# eNode2.net
KiCad netlist of a schematic drawn in EAGLE
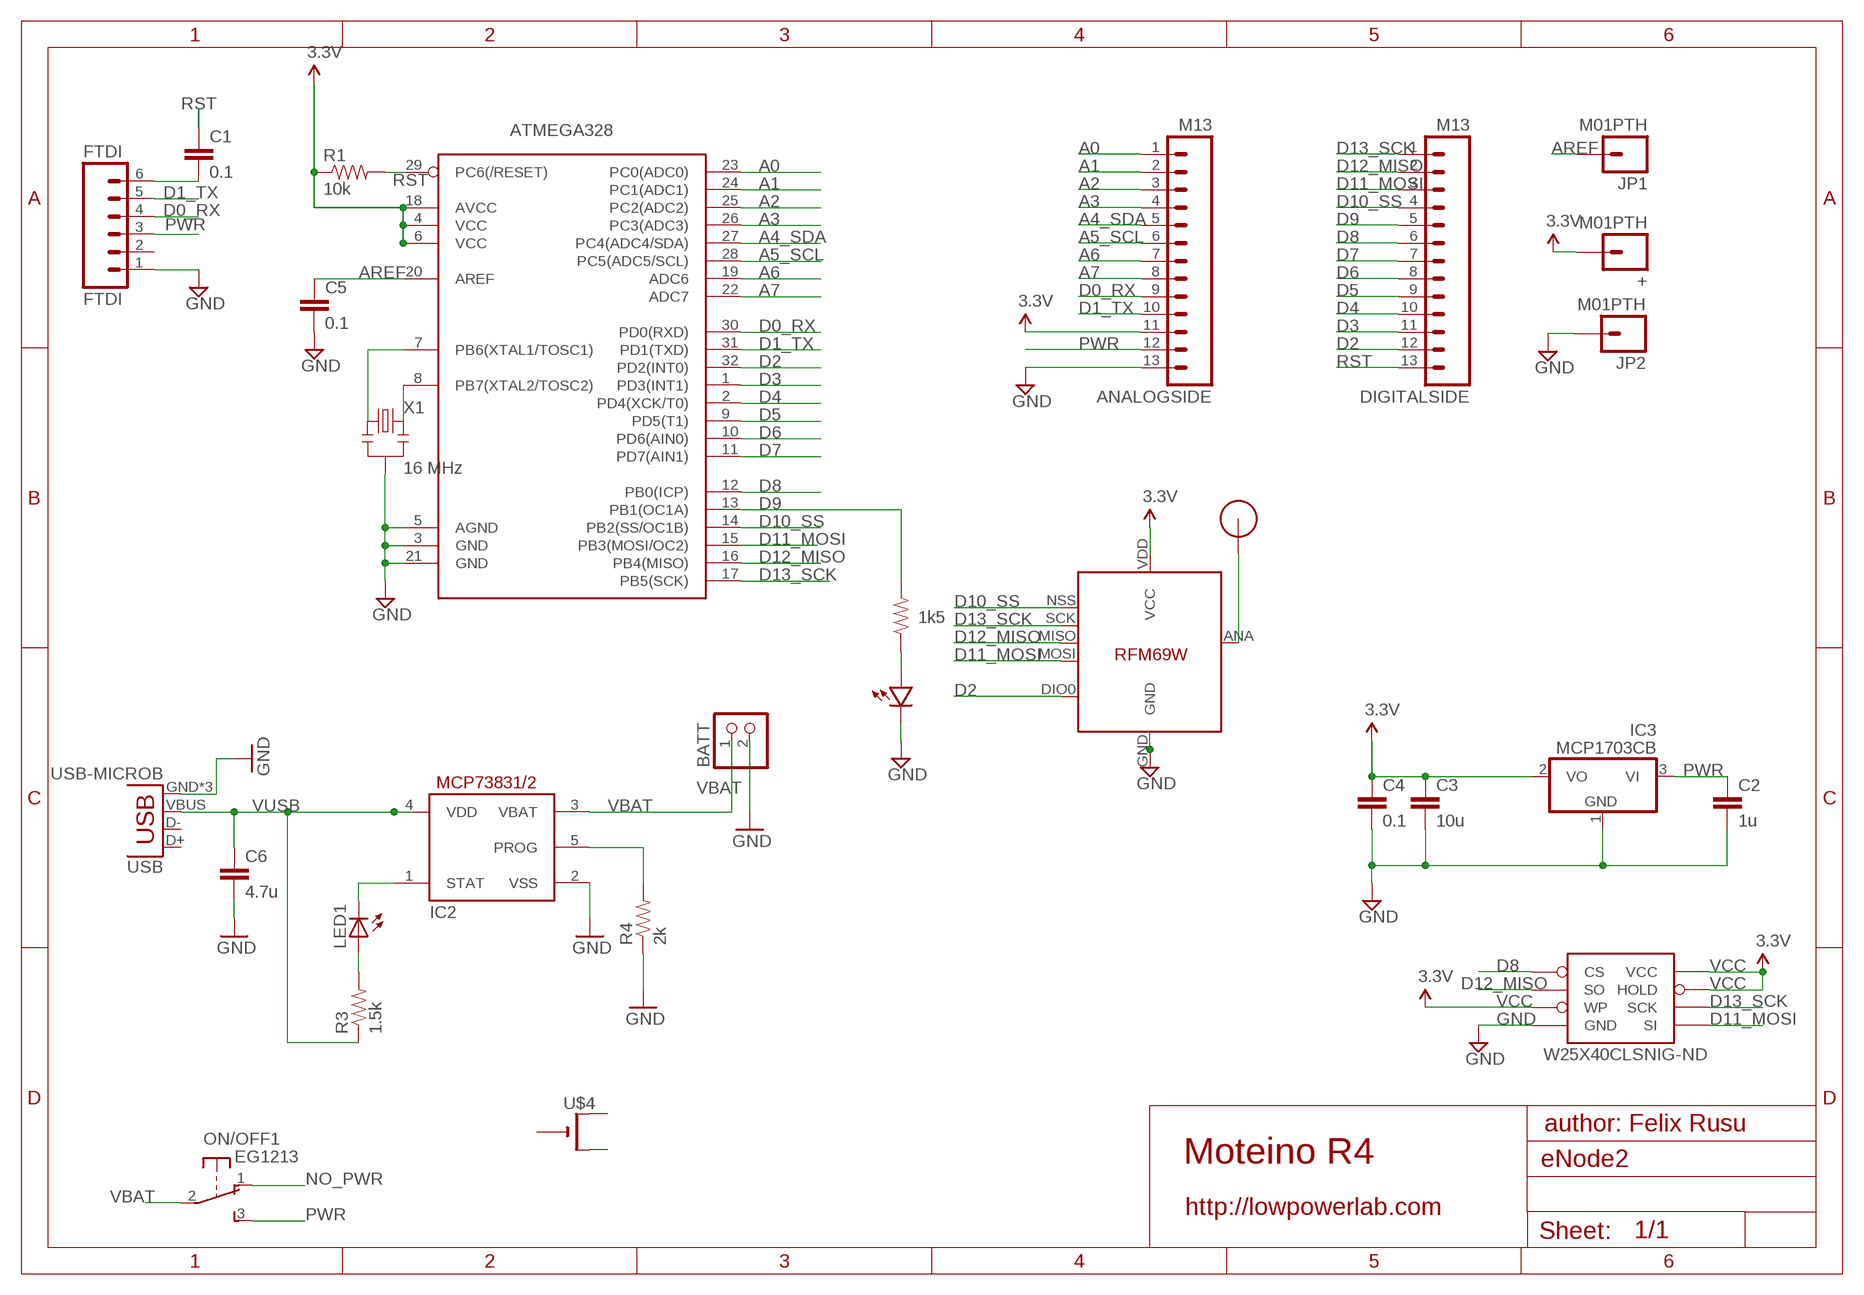
[diagram p0: schematic, sheet 1]

(export (version "E")
  (design (tool "Eeschema 10.0.6"))
  (components
    (comp (ref "+")
      (value "M01PTH")
      (footprint "eagle-import:1X01")
      (libsource (lib "eagle-import") (part "M01PTH"))
    )
    (comp (ref "ANALOGSIDE")
      (value "M13")
      (footprint "eagle-import:1X13")
      (libsource (lib "eagle-import") (part "M13"))
    )
    (comp (ref "ATMEGA328")
      (value "ATMega-328")
      (footprint "eagle-import:TQFP32-08")
      (libsource (lib "eagle-import") (part "ATMEGA168/328TQFP32"))
    )
    (comp (ref "BATT")
      (value "PINHD-1X2")
      (footprint "eagle-import:1X02")
      (libsource (lib "eagle-import") (part "PINHD-1X2"))
    )
    (comp (ref "C1")
      (value "0.1")
      (footprint "eagle-import:0603-CAP")
      (libsource (lib "eagle-import") (part "CAP0603-CAP"))
    )
    (comp (ref "C2")
      (value "1u")
      (footprint "eagle-import:0603-CAP")
      (libsource (lib "eagle-import") (part "CAP0603-CAP"))
    )
    (comp (ref "C3")
      (value "10u")
      (footprint "eagle-import:0805-CAP")
      (libsource (lib "eagle-import") (part "CAP0805-CAP"))
    )
    (comp (ref "C4")
      (value "0.1")
      (footprint "eagle-import:0603-CAP")
      (libsource (lib "eagle-import") (part "CAP0603-CAP"))
    )
    (comp (ref "C5")
      (value "0.1")
      (footprint "eagle-import:0603-CAP")
      (libsource (lib "eagle-import") (part "CAP0603-CAP"))
    )
    (comp (ref "C6")
      (value "4.7u")
      (footprint "eagle-import:0603-CAP")
      (libsource (lib "eagle-import") (part "SparkFun-Passives_CAP0603-CAP"))
    )
    (comp (ref "DIGITALSIDE")
      (value "M13")
      (footprint "eagle-import:1X13")
      (libsource (lib "eagle-import") (part "M13"))
    )
    (comp (ref "FTDI")
      (value "FTDI")
      (footprint "eagle-import:1X06")
      (libsource (lib "eagle-import") (part "M06SIP"))
    )
    (comp (ref "IC2")
      (value "MCP73831/OT")
      (footprint "eagle-import:SOT23-5L")
      (libsource (lib "eagle-import") (part "MCP73831/OT"))
    )
    (comp (ref "IC3")
      (value "MCP1703CB")
      (footprint "eagle-import:SOT23")
      (libsource (lib "eagle-import") (part "MCP1703CB"))
    )
    (comp (ref "JP1")
      (value "M01PTH")
      (footprint "eagle-import:1X01")
      (libsource (lib "eagle-import") (part "M01PTH"))
    )
    (comp (ref "JP2")
      (value "M01PTH")
      (footprint "eagle-import:1X01")
      (libsource (lib "eagle-import") (part "M01PTH"))
    )
    (comp (ref "LED1")
      (value "LEDCHIPLED_0603")
      (footprint "eagle-import:CHIPLED_0603")
      (libsource (lib "eagle-import") (part "LEDCHIPLED_0603"))
    )
    (comp (ref "ON/OFF")
      (value "EG1213")
      (footprint "eagle-import:EG1213")
      (libsource (lib "eagle-import") (part "EG1213"))
    )
    (comp (ref "R1")
      (value "10k")
      (footprint "eagle-import:0603-RES")
      (libsource (lib "eagle-import") (part "RESISTOR0603-RES"))
    )
    (comp (ref "R2")
      (value "1k5")
      (footprint "eagle-import:0603-RES")
      (libsource (lib "eagle-import") (part "RESISTOR0603-RES"))
    )
    (comp (ref "R3")
      (value "1.5k")
      (footprint "eagle-import:0603-RES")
      (libsource (lib "eagle-import") (part "SparkFun-Passives_RESISTOR0603-RES"))
    )
    (comp (ref "R4")
      (value "2k")
      (footprint "eagle-import:0603-RES")
      (libsource (lib "eagle-import") (part "SparkFun-Passives_RESISTOR0603-RES"))
    )
    (comp (ref "U$1")
      (value "RFM12B_ANTENNA")
      (footprint "eagle-import:RFM12B-ANTENNA")
      (libsource (lib "eagle-import") (part "RFM12B_ANTENNA"))
    )
    (comp (ref "U$2")
      (value "LED0603")
      (footprint "eagle-import:0603-LED")
      (libsource (lib "eagle-import") (part "LED0603"))
    )
    (comp (ref "U$4")
      (value "CR2032THM")
      (footprint "eagle-import:CR2032-THRU")
      (libsource (lib "eagle-import") (part "CR2032THM"))
    )
    (comp (ref "U$5")
      (value "RFM69")
      (footprint "eagle-import:RFM69W-MINPADS")
      (libsource (lib "eagle-import") (part "RFM69"))
    )
    (comp (ref "USB")
      (value "USB-MICROB")
      (footprint "eagle-import:USB-MICROB")
      (libsource (lib "eagle-import") (part "USB-MICROB"))
    )
    (comp (ref "W25X40CLSNIG-ND")
      (value "AT25F512BWIDE_5.3MM")
      (footprint "eagle-import:SO08WIDE")
      (libsource (lib "eagle-import") (part "AT25F512BWIDE_5.3MM"))
    )
    (comp (ref "X1")
      (value "16 MHz")
      (footprint "eagle-import:RESONATOR-SMD")
      (libsource (lib "eagle-import") (part "RESONATORSMD"))
    )
  )
  (nets
    (net (code "1") (name "/A0") (class "Default")
      (node (ref "ANALOGSIDE") (pin "1") (pinfunction "1_1") (pintype "passive"))
      (node (ref "ATMEGA328") (pin "23") (pinfunction "PC0(ADC0)_23") (pintype "bidirectional"))
    )
    (net (code "2") (name "/A1") (class "Default")
      (node (ref "ANALOGSIDE") (pin "2") (pinfunction "2_2") (pintype "passive"))
      (node (ref "ATMEGA328") (pin "24") (pinfunction "PC1(ADC1)_24") (pintype "bidirectional"))
    )
    (net (code "3") (name "/A2") (class "Default")
      (node (ref "ANALOGSIDE") (pin "3") (pinfunction "3_3") (pintype "passive"))
      (node (ref "ATMEGA328") (pin "25") (pinfunction "PC2(ADC2)_25") (pintype "bidirectional"))
    )
    (net (code "4") (name "/A3") (class "Default")
      (node (ref "ANALOGSIDE") (pin "4") (pinfunction "4_4") (pintype "passive"))
      (node (ref "ATMEGA328") (pin "26") (pinfunction "PC3(ADC3)_26") (pintype "bidirectional"))
    )
    (net (code "5") (name "/A4_SDA") (class "Default")
      (node (ref "ANALOGSIDE") (pin "5") (pinfunction "5_5") (pintype "passive"))
      (node (ref "ATMEGA328") (pin "27") (pinfunction "PC4(ADC4/SDA)_27") (pintype "bidirectional"))
    )
    (net (code "6") (name "/A5_SCL") (class "Default")
      (node (ref "ANALOGSIDE") (pin "6") (pinfunction "6_6") (pintype "passive"))
      (node (ref "ATMEGA328") (pin "28") (pinfunction "PC5(ADC5/SCL)_28") (pintype "bidirectional"))
    )
    (net (code "7") (name "/A6") (class "Default")
      (node (ref "ANALOGSIDE") (pin "7") (pinfunction "7_7") (pintype "passive"))
      (node (ref "ATMEGA328") (pin "19") (pinfunction "ADC6_19") (pintype "bidirectional"))
    )
    (net (code "8") (name "/A7") (class "Default")
      (node (ref "ANALOGSIDE") (pin "8") (pinfunction "8_8") (pintype "passive"))
      (node (ref "ATMEGA328") (pin "22") (pinfunction "ADC7_22") (pintype "bidirectional"))
    )
    (net (code "9") (name "/AREF") (class "Default")
      (node (ref "ATMEGA328") (pin "20") (pinfunction "AREF_20") (pintype "bidirectional"))
      (node (ref "C5") (pin "1") (pinfunction "1_1") (pintype "passive"))
      (node (ref "JP1") (pin "1") (pinfunction "1_1") (pintype "passive"))
    )
    (net (code "10") (name "/D0_RX") (class "Default")
      (node (ref "ANALOGSIDE") (pin "9") (pinfunction "9_9") (pintype "passive"))
      (node (ref "ATMEGA328") (pin "30") (pinfunction "PD0(RXD)_30") (pintype "bidirectional"))
      (node (ref "FTDI") (pin "4") (pinfunction "4_4") (pintype "passive"))
    )
    (net (code "11") (name "/D1_TX") (class "Default")
      (node (ref "ANALOGSIDE") (pin "10") (pinfunction "10_10") (pintype "passive"))
      (node (ref "ATMEGA328") (pin "31") (pinfunction "PD1(TXD)_31") (pintype "bidirectional"))
      (node (ref "FTDI") (pin "5") (pinfunction "5_5") (pintype "passive"))
    )
    (net (code "12") (name "/D2") (class "Default")
      (node (ref "ATMEGA328") (pin "32") (pinfunction "PD2(INT0)_32") (pintype "bidirectional"))
      (node (ref "DIGITALSIDE") (pin "12") (pinfunction "12_12") (pintype "passive"))
      (node (ref "U$5") (pin "DIO0") (pinfunction "DIO0_DIO0") (pintype "open_collector"))
    )
    (net (code "13") (name "/D3") (class "Default")
      (node (ref "ATMEGA328") (pin "1") (pinfunction "PD3(INT1)_1") (pintype "bidirectional"))
      (node (ref "DIGITALSIDE") (pin "11") (pinfunction "11_11") (pintype "passive"))
    )
    (net (code "14") (name "/D4") (class "Default")
      (node (ref "ATMEGA328") (pin "2") (pinfunction "PD4(XCK/T0)_2") (pintype "bidirectional"))
      (node (ref "DIGITALSIDE") (pin "10") (pinfunction "10_10") (pintype "passive"))
    )
    (net (code "15") (name "/D5") (class "Default")
      (node (ref "ATMEGA328") (pin "9") (pinfunction "PD5(T1)_9") (pintype "bidirectional"))
      (node (ref "DIGITALSIDE") (pin "9") (pinfunction "9_9") (pintype "passive"))
    )
    (net (code "16") (name "/D6") (class "Default")
      (node (ref "ATMEGA328") (pin "10") (pinfunction "PD6(AIN0)_10") (pintype "bidirectional"))
      (node (ref "DIGITALSIDE") (pin "8") (pinfunction "8_8") (pintype "passive"))
    )
    (net (code "17") (name "/D7") (class "Default")
      (node (ref "ATMEGA328") (pin "11") (pinfunction "PD7(AIN1)_11") (pintype "bidirectional"))
      (node (ref "DIGITALSIDE") (pin "7") (pinfunction "7_7") (pintype "passive"))
    )
    (net (code "18") (name "/D8") (class "Default")
      (node (ref "ATMEGA328") (pin "12") (pinfunction "PB0(ICP)_12") (pintype "bidirectional"))
      (node (ref "DIGITALSIDE") (pin "6") (pinfunction "6_6") (pintype "passive"))
      (node (ref "W25X40CLSNIG-ND") (pin "1") (pinfunction "CS_1") (pintype "bidirectional"))
    )
    (net (code "19") (name "/D9") (class "Default")
      (node (ref "ATMEGA328") (pin "13") (pinfunction "PB1(OC1A)_13") (pintype "bidirectional"))
      (node (ref "DIGITALSIDE") (pin "5") (pinfunction "5_5") (pintype "passive"))
      (node (ref "R2") (pin "2") (pinfunction "2_2") (pintype "passive"))
    )
    (net (code "20") (name "/D10_SS") (class "Default")
      (node (ref "ATMEGA328") (pin "14") (pinfunction "PB2(SS/OC1B)_14") (pintype "bidirectional"))
      (node (ref "DIGITALSIDE") (pin "4") (pinfunction "4_4") (pintype "passive"))
      (node (ref "U$5") (pin "NSS") (pinfunction "SEL_NSS") (pintype "input"))
    )
    (net (code "21") (name "/D11_MOSI") (class "Default")
      (node (ref "ATMEGA328") (pin "15") (pinfunction "PB3(MOSI/OC2)_15") (pintype "bidirectional"))
      (node (ref "DIGITALSIDE") (pin "3") (pinfunction "3_3") (pintype "passive"))
      (node (ref "U$5") (pin "MOSI") (pinfunction "MOSI_MOSI") (pintype "output"))
      (node (ref "W25X40CLSNIG-ND") (pin "5") (pinfunction "SI_5") (pintype "bidirectional"))
    )
    (net (code "22") (name "/D12_MISO") (class "Default")
      (node (ref "ATMEGA328") (pin "16") (pinfunction "PB4(MISO)_16") (pintype "bidirectional"))
      (node (ref "DIGITALSIDE") (pin "2") (pinfunction "2_2") (pintype "passive"))
      (node (ref "U$5") (pin "MISO") (pinfunction "MISO_MISO") (pintype "input"))
      (node (ref "W25X40CLSNIG-ND") (pin "2") (pinfunction "SO_2") (pintype "bidirectional"))
    )
    (net (code "23") (name "/D13_SCK") (class "Default")
      (node (ref "ATMEGA328") (pin "17") (pinfunction "PB5(SCK)_17") (pintype "bidirectional"))
      (node (ref "DIGITALSIDE") (pin "1") (pinfunction "1_1") (pintype "passive"))
      (node (ref "U$5") (pin "SCK") (pinfunction "SCK_SCK") (pintype "input"))
      (node (ref "W25X40CLSNIG-ND") (pin "6") (pinfunction "SCK_6") (pintype "bidirectional"))
    )
    (net (code "24") (name "/NO_PWR") (class "Default")
      (node (ref "ON/OFF") (pin "1") (pinfunction "O_1") (pintype "passive"))
    )
    (net (code "25") (name "/PWR") (class "Default")
      (node (ref "ANALOGSIDE") (pin "12") (pinfunction "12_12") (pintype "passive"))
      (node (ref "C2") (pin "1") (pinfunction "1_1") (pintype "passive"))
      (node (ref "FTDI") (pin "3") (pinfunction "3_3") (pintype "passive"))
      (node (ref "IC3") (pin "3") (pinfunction "VI_3") (pintype "input"))
      (node (ref "ON/OFF") (pin "3") (pinfunction "S_3") (pintype "passive"))
    )
    (net (code "26") (name "/RST") (class "Default")
      (node (ref "ATMEGA328") (pin "29") (pinfunction "PC6(/RESET)_29") (pintype "bidirectional"))
      (node (ref "C1") (pin "1") (pinfunction "1_1") (pintype "passive"))
      (node (ref "DIGITALSIDE") (pin "13") (pinfunction "13_13") (pintype "passive"))
      (node (ref "R1") (pin "2") (pinfunction "2_2") (pintype "passive"))
    )
    (net (code "27") (name "/VBAT") (class "Default")
      (node (ref "BATT") (pin "1") (pinfunction "1_1") (pintype "passive"))
      (node (ref "IC2") (pin "3") (pinfunction "VBAT_3") (pintype "bidirectional"))
      (node (ref "ON/OFF") (pin "2") (pinfunction "P_2") (pintype "passive"))
    )
    (net (code "28") (name "/VUSB") (class "Default")
      (node (ref "C6") (pin "1") (pinfunction "1_1") (pintype "passive"))
      (node (ref "IC2") (pin "4") (pinfunction "VDD_4") (pintype "power_in"))
      (node (ref "R3") (pin "1") (pinfunction "1_1") (pintype "passive"))
      (node (ref "USB") (pin "VBUS") (pinfunction "VBUS_VBUS") (pintype "bidirectional"))
    )
    (net (code "29") (name "3.3V") (class "Default")
      (node (ref "+") (pin "1") (pinfunction "1_1") (pintype "passive"))
      (node (ref "ANALOGSIDE") (pin "11") (pinfunction "11_11") (pintype "passive"))
      (node (ref "ATMEGA328") (pin "18") (pinfunction "AVCC_18") (pintype "bidirectional"))
      (node (ref "ATMEGA328") (pin "4") (pinfunction "VCC_4") (pintype "bidirectional"))
      (node (ref "ATMEGA328") (pin "6") (pinfunction "VCC_6") (pintype "bidirectional"))
      (node (ref "C3") (pin "1") (pinfunction "1_1") (pintype "passive"))
      (node (ref "C4") (pin "1") (pinfunction "1_1") (pintype "passive"))
      (node (ref "IC3") (pin "2") (pinfunction "VO_2") (pintype "passive"))
      (node (ref "R1") (pin "1") (pinfunction "1_1") (pintype "passive"))
      (node (ref "U$5") (pin "VDD") (pinfunction "VCC_VDD") (pintype "power_in"))
      (node (ref "W25X40CLSNIG-ND") (pin "3") (pinfunction "WP_3") (pintype "bidirectional"))
      (node (ref "W25X40CLSNIG-ND") (pin "7") (pinfunction "HOLD_7") (pintype "bidirectional"))
      (node (ref "W25X40CLSNIG-ND") (pin "8") (pinfunction "VCC_8") (pintype "bidirectional"))
    )
    (net (code "30") (name "GND") (class "Default")
      (node (ref "ANALOGSIDE") (pin "13") (pinfunction "13_13") (pintype "passive"))
      (node (ref "ATMEGA328") (pin "21") (pinfunction "GND_21") (pintype "bidirectional"))
      (node (ref "ATMEGA328") (pin "3") (pinfunction "GND_3") (pintype "bidirectional"))
      (node (ref "ATMEGA328") (pin "5") (pinfunction "AGND_5") (pintype "bidirectional"))
      (node (ref "BATT") (pin "2") (pinfunction "2_2") (pintype "passive"))
      (node (ref "C2") (pin "2") (pinfunction "2_2") (pintype "passive"))
      (node (ref "C3") (pin "2") (pinfunction "2_2") (pintype "passive"))
      (node (ref "C4") (pin "2") (pinfunction "2_2") (pintype "passive"))
      (node (ref "C5") (pin "2") (pinfunction "2_2") (pintype "passive"))
      (node (ref "C6") (pin "2") (pinfunction "2_2") (pintype "passive"))
      (node (ref "FTDI") (pin "1") (pinfunction "1_1") (pintype "passive"))
      (node (ref "IC2") (pin "2") (pinfunction "VSS_2") (pintype "power_in"))
      (node (ref "IC3") (pin "1") (pinfunction "GND_1") (pintype "passive"))
      (node (ref "JP2") (pin "1") (pinfunction "1_1") (pintype "passive"))
      (node (ref "R4") (pin "1") (pinfunction "1_1") (pintype "passive"))
      (node (ref "U$2") (pin "MINUS") (pinfunction "MINUS_MINUS") (pintype "passive"))
      (node (ref "U$5") (pin "GND") (pinfunction "GND_GND") (pintype "power_in"))
      (node (ref "USB") (pin "GND") (pinfunction "GND_GND") (pintype "bidirectional"))
      (node (ref "USB") (pin "MT1") (pinfunction "GND_MT1") (pintype "bidirectional"))
      (node (ref "USB") (pin "MT2") (pinfunction "GND_MT2") (pintype "bidirectional"))
      (node (ref "W25X40CLSNIG-ND") (pin "4") (pinfunction "GND_4") (pintype "bidirectional"))
      (node (ref "X1") (pin "2") (pinfunction "2_2") (pintype "passive"))
    )
    (net (code "31") (name "Net-(ATMEGA328-PB6(XTAL1{slash}TOSC1))") (class "Default")
      (node (ref "ATMEGA328") (pin "7") (pinfunction "PB6(XTAL1/TOSC1)_7") (pintype "bidirectional"))
      (node (ref "X1") (pin "1") (pinfunction "1_1") (pintype "passive"))
    )
    (net (code "32") (name "Net-(ATMEGA328-PB7(XTAL2{slash}TOSC2))") (class "Default")
      (node (ref "ATMEGA328") (pin "8") (pinfunction "PB7(XTAL2/TOSC2)_8") (pintype "bidirectional"))
      (node (ref "X1") (pin "3") (pinfunction "3_3") (pintype "passive"))
    )
    (net (code "33") (name "Net-(C1-Pad2)") (class "Default")
      (node (ref "C1") (pin "2") (pinfunction "2_2") (pintype "passive"))
      (node (ref "FTDI") (pin "6") (pinfunction "6_6") (pintype "passive"))
    )
    (net (code "34") (name "Net-(IC2-PROG)") (class "Default")
      (node (ref "IC2") (pin "5") (pinfunction "PROG_5") (pintype "input"))
      (node (ref "R4") (pin "2") (pinfunction "2_2") (pintype "passive"))
    )
    (net (code "35") (name "Net-(IC2-STAT)") (class "Default")
      (node (ref "IC2") (pin "1") (pinfunction "STAT_1") (pintype "output"))
      (node (ref "LED1") (pin "C") (pinfunction "C_C") (pintype "passive"))
    )
    (net (code "36") (name "Net-(LED1-PadA)") (class "Default")
      (node (ref "LED1") (pin "A") (pinfunction "A_A") (pintype "passive"))
      (node (ref "R3") (pin "2") (pinfunction "2_2") (pintype "passive"))
    )
    (net (code "37") (name "Net-(R2-Pad1)") (class "Default")
      (node (ref "R2") (pin "1") (pinfunction "1_1") (pintype "passive"))
      (node (ref "U$2") (pin "PLUS") (pinfunction "PLUS_PLUS") (pintype "passive"))
    )
    (net (code "38") (name "Net-(U$1-1)") (class "Default")
      (node (ref "U$1") (pin "P$1") (pinfunction "1_P$1") (pintype "bidirectional"))
      (node (ref "U$5") (pin "ANA") (pinfunction "ANT_ANA") (pintype "passive"))
    )
    (net (code "39") (name "unconnected-(FTDI-Pad2)") (class "Default")
      (node (ref "FTDI") (pin "2") (pinfunction "2_2") (pintype "passive"))
    )
    (net (code "40") (name "unconnected-(U$4-+-Pad+1)") (class "Default")
      (node (ref "U$4") (pin "+1") (pinfunction "+_+1") (pintype "passive"))
    )
    (net (code "41") (name "unconnected-(U$4-+1-Pad+2)") (class "Default")
      (node (ref "U$4") (pin "+2") (pinfunction "+1_+2") (pintype "passive"))
    )
    (net (code "42") (name "unconnected-(U$4-Pad-)") (class "Default")
      (node (ref "U$4") (pin "-") (pinfunction "-_-") (pintype "passive"))
    )
    (net (code "43") (name "unconnected-(USB-PadD+)") (class "Default")
      (node (ref "USB") (pin "D+") (pinfunction "D+_D+") (pintype "bidirectional"))
    )
    (net (code "44") (name "unconnected-(USB-PadD-)") (class "Default")
      (node (ref "USB") (pin "D-") (pinfunction "D-_D-") (pintype "bidirectional"))
    )
  )
)
